# main.net
KiCad netlist of a schematic drawn in Altium Designer
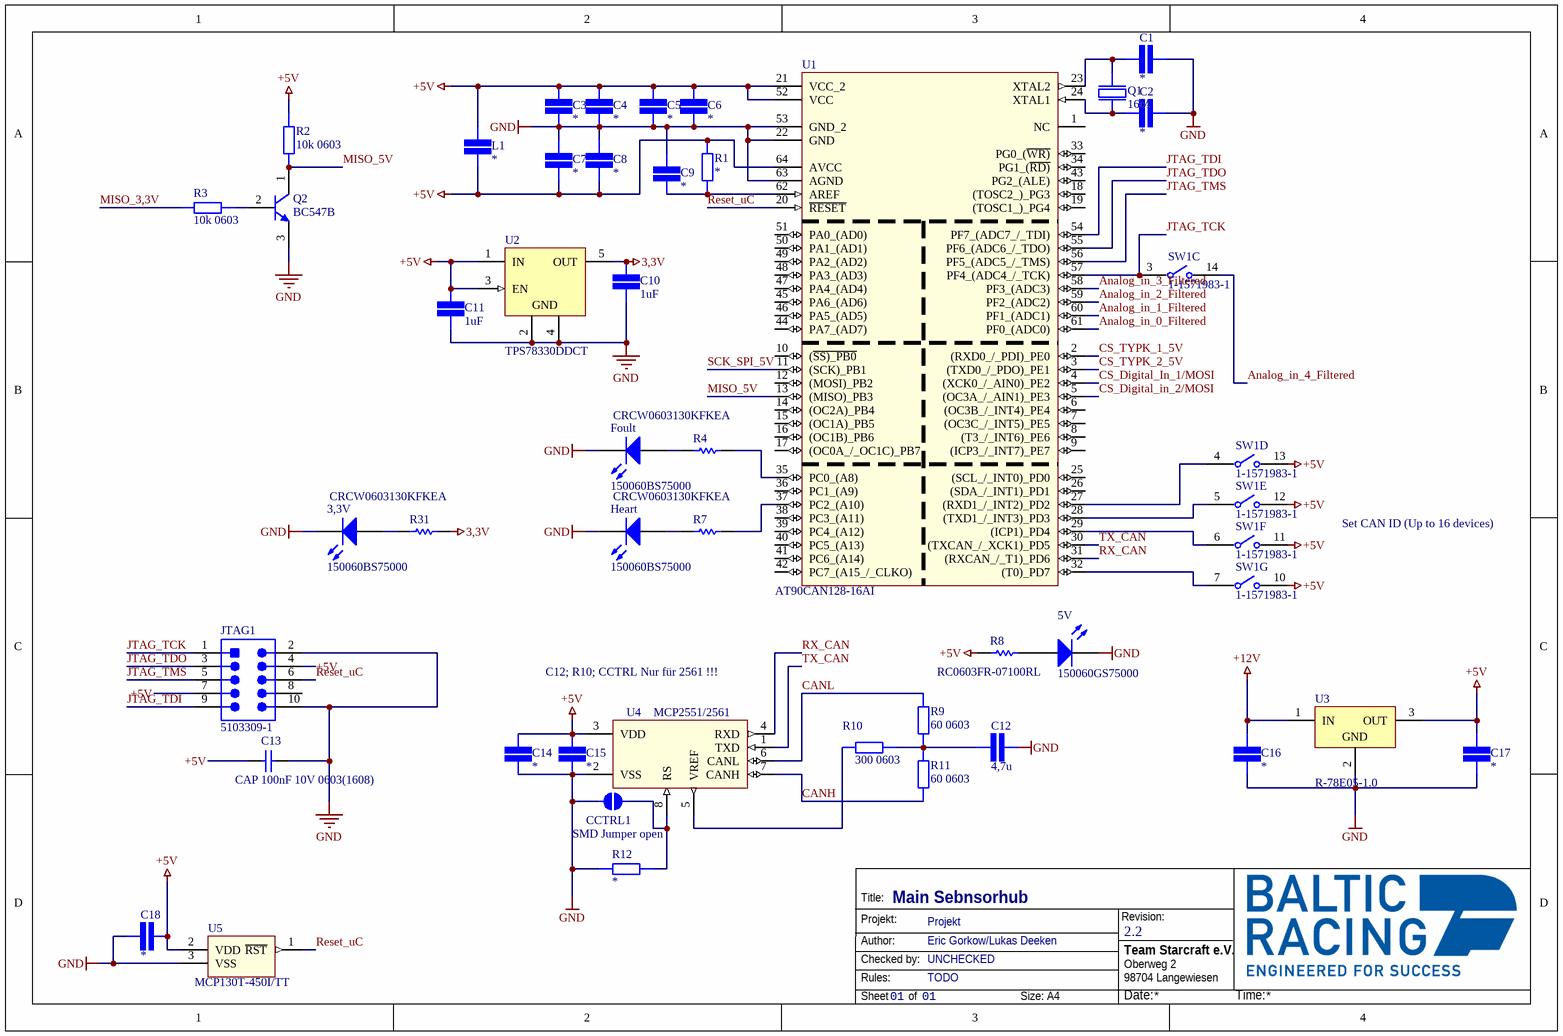
[diagram p0: main.SchDoc]

(export (version "E")
  (design (tool "Eeschema 10.0.6"))
  (components
    (comp (ref "3,3V")
      (value "150060BS75000")
      (footprint "0603_A")
      (description "SMD mono-color Chip LED, WL-SMCW, Blue")
      (fields (field (name "MANUFACTURER") "Wuerth Elektronik"))
      (libsource (lib "Altium Content Vault") (part "WE-LED_K1A2-2"))
    )
    (comp (ref "5V")
      (value "150060GS75000")
      (footprint "0603_A")
      (description "SMD mono-color Chip LED, WL-SMCW, Green")
      (fields (field (name "MANUFACTURER") "Wuerth Elektronik"))
      (libsource (lib "Altium Content Vault") (part "WE-LED_K1A2-2"))
    )
    (comp (ref "C1")
      (value "SMD Capacitor")
      (footprint "CAP 0603/1608")
      (description "Capacitor with multiple Footprints")
      (fields (field (name "ALTIUM_VALUE") "*"))
      (libsource (lib "Standardbauteile") (part "SMD Capacitor"))
    )
    (comp (ref "C2")
      (value "SMD Capacitor")
      (footprint "CAP 0603/1608")
      (description "Capacitor with multiple Footprints")
      (fields (field (name "ALTIUM_VALUE") "*"))
      (libsource (lib "Standardbauteile") (part "SMD Capacitor"))
    )
    (comp (ref "C3")
      (value "SMD Capacitor")
      (footprint "CAP 0603/1608")
      (description "Capacitor with multiple Footprints")
      (fields (field (name "ALTIUM_VALUE") "*"))
      (libsource (lib "") (part "SMD Capacitor_1"))
    )
    (comp (ref "C4")
      (value "SMD Capacitor")
      (footprint "CAP 0603/1608")
      (description "Capacitor with multiple Footprints")
      (fields (field (name "ALTIUM_VALUE") "*"))
      (libsource (lib "") (part "SMD Capacitor_1"))
    )
    (comp (ref "C5")
      (value "SMD Capacitor")
      (footprint "CAP 0603/1608")
      (description "Capacitor with multiple Footprints")
      (fields (field (name "ALTIUM_VALUE") "*"))
      (libsource (lib "") (part "SMD Capacitor_1"))
    )
    (comp (ref "C6")
      (value "SMD Capacitor")
      (footprint "CAP 0603/1608")
      (description "Capacitor with multiple Footprints")
      (fields (field (name "ALTIUM_VALUE") "*"))
      (libsource (lib "") (part "SMD Capacitor_1"))
    )
    (comp (ref "C7")
      (value "SMD Capacitor")
      (footprint "CAP 0603/1608")
      (description "Capacitor with multiple Footprints")
      (fields (field (name "ALTIUM_VALUE") "*"))
      (libsource (lib "") (part "SMD Capacitor_1"))
    )
    (comp (ref "C8")
      (value "SMD Capacitor")
      (footprint "CAP 0603/1608")
      (description "Capacitor with multiple Footprints")
      (fields (field (name "ALTIUM_VALUE") "*"))
      (libsource (lib "") (part "SMD Capacitor_1"))
    )
    (comp (ref "C9")
      (value "SMD Capacitor")
      (footprint "CAP 0603/1608")
      (description "Capacitor with multiple Footprints")
      (fields (field (name "ALTIUM_VALUE") "*"))
      (libsource (lib "") (part "SMD Capacitor_1"))
    )
    (comp (ref "C10")
      (value "1uF")
      (footprint "CAP 0603/1608")
      (description "Capacitor with multiple Footprints")
      (fields (field (name "Comment") "SMD Capacitor 1uF"))
      (libsource (lib "") (part "SMD Capacitor_1"))
    )
    (comp (ref "C11")
      (value "1uF")
      (footprint "CAP 0603/1608")
      (description "Capacitor with multiple Footprints")
      (fields (field (name "Comment") "SMD Capacitor 1uF"))
      (libsource (lib "") (part "SMD Capacitor_1"))
    )
    (comp (ref "C12")
      (value "4,7u")
      (footprint "CAP 0603/1608")
      (description "Capacitor with multiple Footprints")
      (fields (field (name "Comment") "SMD Capacitor"))
      (libsource (lib "") (part "SMD Capacitor_2"))
    )
    (comp (ref "C13")
      (value "CAP 100nF 10V 0603(1608)")
      (footprint "CAPC0603(1608)100_L")
      (description "CAP 100nF 10V ±5% 0603 (1608 Metric) Thickness 1mm SMD")
      (fields (field (name "TOLERANCE") "Â±5%"))
      (libsource (lib "Altium Content Vault") (part "CAP"))
    )
    (comp (ref "C14")
      (value "SMD Capacitor")
      (footprint "CAP 0603/1608")
      (description "Capacitor with multiple Footprints")
      (fields (field (name "ALTIUM_VALUE") "*"))
      (libsource (lib "") (part "SMD Capacitor_1"))
    )
    (comp (ref "C15")
      (value "SMD Capacitor")
      (footprint "CAP 0603/1608")
      (description "Capacitor with multiple Footprints")
      (fields (field (name "ALTIUM_VALUE") "*"))
      (libsource (lib "") (part "SMD Capacitor_1"))
    )
    (comp (ref "C16")
      (value "SMD Capacitor")
      (footprint "CAP 0603/1608")
      (description "Capacitor with multiple Footprints")
      (fields (field (name "ALTIUM_VALUE") "*"))
      (libsource (lib "") (part "SMD Capacitor_1"))
    )
    (comp (ref "C17")
      (value "SMD Capacitor")
      (footprint "CAP 0603/1608")
      (description "Capacitor with multiple Footprints")
      (fields (field (name "ALTIUM_VALUE") "*"))
      (libsource (lib "") (part "SMD Capacitor_1"))
    )
    (comp (ref "C18")
      (value "SMD Capacitor")
      (footprint "CAP 0603/1608")
      (description "Capacitor with multiple Footprints")
      (fields (field (name "ALTIUM_VALUE") "*"))
      (libsource (lib "Standardbauteile") (part "SMD Capacitor"))
    )
    (comp (ref "CCTRL1")
      (value "SMD Jumper open")
      (footprint "SMD-JUMPER-OPEN")
      (libsource (lib "Standardbauteile") (part "SMD Jumper open"))
    )
    (comp (ref "Foult")
      (value "150060BS75000")
      (footprint "0603_A")
      (description "SMD mono-color Chip LED, WL-SMCW, Blue")
      (fields (field (name "MANUFACTURER") "Wuerth Elektronik"))
      (libsource (lib "Altium Content Vault") (part "WE-LED_K1A2-2"))
    )
    (comp (ref "Heart")
      (value "150060BS75000")
      (footprint "0603_A")
      (description "SMD mono-color Chip LED, WL-SMCW, Blue")
      (fields (field (name "MANUFACTURER") "Wuerth Elektronik"))
      (libsource (lib "Altium Content Vault") (part "WE-LED_K1A2-2"))
    )
    (comp (ref "JTAG1")
      (value "5103309-1")
      (footprint "TECO-5103309-1_V")
      (fields (field (name "MANUFACTURER") "TE Connectivity"))
      (libsource (lib "Altium Content Vault") (part "CN-2P-M-R10"))
    )
    (comp (ref "L1")
      (value "SMD Capacitor")
      (footprint "CAP 0603/1608")
      (description "Capacitor with multiple Footprints")
      (fields (field (name "ALTIUM_VALUE") "*"))
      (libsource (lib "") (part "SMD Capacitor_1"))
    )
    (comp (ref "Q1")
      (value "16M")
      (footprint "NDK NX5032GA")
      (description "16 MHz Quartz")
      (libsource (lib "Standardbauteile") (part "16 MHz Quartz"))
    )
    (comp (ref "Q2")
      (value "BC547B")
      (footprint "ONSC-TO-92-3-29-11")
      (description "Amplifier Transistor, NPN Silicon, 3-Pin TO-92, Bulk Box")
      (fields (field (name "MANUFACTURER") "On Semiconductor"))
      (libsource (lib "Altium Content Vault") (part "ONSC-NPN-C1B2E3-3"))
    )
    (comp (ref "R1")
      (value "SMD Resistor")
      (footprint "STACKPOLE CSR0603")
      (description "Resistor with multiple footprints")
      (fields (field (name "ALTIUM_VALUE") "*"))
      (libsource (lib "Standardbauteile") (part "SMD Resistor"))
    )
    (comp (ref "R2")
      (value "10k 0603")
      (footprint "STACKPOLE CSR0603")
      (description "Resistor with multiple footprints")
      (fields (field (name "Comment") "SMD Resistor"))
      (libsource (lib "Standardbauteile") (part "SMD Resistor"))
    )
    (comp (ref "R3")
      (value "10k 0603")
      (footprint "STACKPOLE CSR0603")
      (description "Resistor with multiple footprints")
      (fields (field (name "Comment") "SMD Resistor"))
      (libsource (lib "Standardbauteile") (part "SMD Resistor"))
    )
    (comp (ref "R4")
      (value "CRCW0603130KFKEA")
      (footprint "RESC1609X50X30NL10T20")
      (fields (field (name "MANUFACTURER") "Vishay Dale"))
      (libsource (lib "Altium Content Vault") (part "RES"))
    )
    (comp (ref "R7")
      (value "CRCW0603130KFKEA")
      (footprint "RESC1609X50X30NL10T20")
      (fields (field (name "MANUFACTURER") "Vishay Dale"))
      (libsource (lib "Altium Content Vault") (part "RES"))
    )
    (comp (ref "R8")
      (value "RC0603FR-07100RL")
      (footprint "RESC1608X55X25ML10T15")
      (description "Chip Resistor, 100 Ohm, +/- 1%, 0.1 W, -55 to 155 degC, 0603 (1608 Metric), RoHS, Tape and Reel")
      (fields (field (name "TOLERANCE") "1%") (field (name "MANUFACTURER") "Yageo"))
      (libsource (lib "Altium Content Vault") (part "RES-2"))
    )
    (comp (ref "R9")
      (value "60 0603")
      (footprint "STACKPOLE CSR0603")
      (description "Resistor with multiple footprints")
      (fields (field (name "Comment") "SMD Resistor"))
      (libsource (lib "Standardbauteile") (part "SMD Resistor"))
    )
    (comp (ref "R10")
      (value "300 0603")
      (footprint "STACKPOLE CSR0603")
      (description "Resistor with multiple footprints")
      (fields (field (name "Comment") "SMD Resistor"))
      (libsource (lib "Standardbauteile") (part "SMD Resistor"))
    )
    (comp (ref "R11")
      (value "60 0603")
      (footprint "STACKPOLE CSR0603")
      (description "Resistor with multiple footprints")
      (fields (field (name "Comment") "SMD Resistor"))
      (libsource (lib "Standardbauteile") (part "SMD Resistor"))
    )
    (comp (ref "R12")
      (value "SMD Resistor")
      (footprint "STACKPOLE CSR0603")
      (description "Resistor with multiple footprints")
      (fields (field (name "ALTIUM_VALUE") "*"))
      (libsource (lib "Standardbauteile") (part "SMD Resistor"))
    )
    (comp (ref "R31")
      (value "CRCW0603130KFKEA")
      (footprint "RESC1609X50X30NL10T20")
      (fields (field (name "MANUFACTURER") "Vishay Dale"))
      (libsource (lib "Altium Content Vault") (part "RES"))
    )
    (comp (ref "SW1")
      (value "1-1571983-1")
      (footprint "FP-1-1571983-1-MFG")
      (description "SWITCH SLIDE DIP SPST 25MA 24V")
      (fields
        (field (name "MANUFACTURER") "TE Connectivity")
        (field (name "OCTOPART") "https://octopart.com/1-1571983-1-te+connectivity-40115518")
      )
      (libsource (lib "Altium Content Vault") (part "970e54b12a704161c1b4a03f85903bf"))
    )
    (comp (ref "U1")
      (value "AT90CAN128-16AI")
      (footprint "*QFP80P1600X1600X120-64N")
      (description "Ic Mcu 8bit 128kb Flash 64tqfp")
      (fields (field (name "MF") "Microchip"))
      (libsource (lib "Eric") (part "AT90CAN128-16AI"))
    )
    (comp (ref "U2")
      (value "TPS78330DDCT")
      (footprint "DDC0005A_L")
      (fields (field (name "MANUFACTURER") "Texas Instruments"))
      (libsource (lib "Altium Content Vault") (part "TI-TPS78XXX-DDC5"))
    )
    (comp (ref "U3")
      (value "R-78E05-1.0")
      (footprint "SIP3_RECOM")
      (description "Nonisolated 5V Switchmode converter")
      (libsource (lib "Standardbauteile") (part "R-78E05-1.0"))
    )
    (comp (ref "U4")
      (value "MCP2551/2561")
      (footprint "*SOIC127P600X175-8N")
      (description "MCP2551 Series 5.5 V 1 Mb/s Surface Mount High-Speed CAN Transceiver - SOIC-8")
      (fields (field (name "MP") "MCP2551-I/SN") (field (name "MF") "Microchip"))
      (libsource (lib "Eric") (part "MCP2551-I/SN"))
    )
    (comp (ref "U5")
      (value "MCP130T-450I/TT")
      (footprint "*SOT95P237X112-3N")
      (description "System Supervisors - Power Supply Monitors with Reset Generators Open Drain Low")
      (fields (field (name "MF") "Microchip") (field (name "MP") "MCP120T-450I/TT"))
      (libsource (lib "Eric") (part "MCP130T-450I/TT"))
    )
  )
  (nets
    (net (code "1") (name "+5V") (class "Default")
      (node (ref "C11") (pin "2") (pinfunction "2_2") (pintype "passive"))
      (node (ref "C13") (pin "1") (pinfunction "1_1") (pintype "passive"))
      (node (ref "C14") (pin "2") (pinfunction "2_2") (pintype "passive"))
      (node (ref "C15") (pin "2") (pinfunction "2_2") (pintype "passive"))
      (node (ref "C17") (pin "2") (pinfunction "2_2") (pintype "passive"))
      (node (ref "C18") (pin "1") (pinfunction "1_1") (pintype "passive"))
      (node (ref "C3") (pin "2") (pinfunction "2_2") (pintype "passive"))
      (node (ref "C4") (pin "2") (pinfunction "2_2") (pintype "passive"))
      (node (ref "C5") (pin "2") (pinfunction "2_2") (pintype "passive"))
      (node (ref "C6") (pin "2") (pinfunction "2_2") (pintype "passive"))
      (node (ref "C7") (pin "1") (pinfunction "1_1") (pintype "passive"))
      (node (ref "C8") (pin "1") (pinfunction "1_1") (pintype "passive"))
      (node (ref "JTAG1") (pin "4") (pinfunction "4_4") (pintype "passive"))
      (node (ref "JTAG1") (pin "7") (pinfunction "7_7") (pintype "passive"))
      (node (ref "L1") (pin "1") (pinfunction "1_1") (pintype "passive"))
      (node (ref "L1") (pin "2") (pinfunction "2_2") (pintype "passive"))
      (node (ref "R1") (pin "2") (pinfunction "2_2") (pintype "passive"))
      (node (ref "R2") (pin "1") (pinfunction "1_1") (pintype "passive"))
      (node (ref "R8") (pin "1") (pinfunction "1_1") (pintype "passive"))
      (node (ref "SW1") (pin "10") (pinfunction "10_10") (pintype "passive"))
      (node (ref "SW1") (pin "11") (pinfunction "11_11") (pintype "passive"))
      (node (ref "SW1") (pin "12") (pinfunction "12_12") (pintype "passive"))
      (node (ref "SW1") (pin "13") (pinfunction "13_13") (pintype "passive"))
      (node (ref "U1") (pin "21") (pinfunction "VCC_2_21") (pintype "power_in"))
      (node (ref "U1") (pin "52") (pinfunction "VCC_52") (pintype "power_in"))
      (node (ref "U1") (pin "64") (pinfunction "AVCC_64") (pintype "power_in"))
      (node (ref "U2") (pin "1") (pinfunction "IN_1") (pintype "power_in"))
      (node (ref "U2") (pin "3") (pinfunction "EN_3") (pintype "input"))
      (node (ref "U3") (pin "3") (pinfunction "OUT_3") (pintype "power_in"))
      (node (ref "U4") (pin "3") (pinfunction "VDD_3") (pintype "power_in"))
      (node (ref "U5") (pin "2") (pinfunction "VDD_2") (pintype "power_in"))
    )
    (net (code "2") (name "+12V") (class "Default")
      (node (ref "C16") (pin "2") (pinfunction "2_2") (pintype "passive"))
      (node (ref "U3") (pin "1") (pinfunction "IN_1") (pintype "power_in"))
    )
    (net (code "3") (name "/Analog_in_0_Filtered") (class "Default")
      (node (ref "U1") (pin "61") (pinfunction "PF0_(ADC0)_61") (pintype "bidirectional"))
    )
    (net (code "4") (name "/Analog_in_1_Filtered") (class "Default")
      (node (ref "U1") (pin "60") (pinfunction "PF1_(ADC1)_60") (pintype "bidirectional"))
    )
    (net (code "5") (name "/Analog_in_2_Filtered") (class "Default")
      (node (ref "U1") (pin "59") (pinfunction "PF2_(ADC2)_59") (pintype "bidirectional"))
    )
    (net (code "6") (name "/Analog_in_3_Filtered") (class "Default")
      (node (ref "U1") (pin "58") (pinfunction "PF3_(ADC3)_58") (pintype "bidirectional"))
    )
    (net (code "7") (name "/Analog_in_4_Filtered") (class "Default")
      (node (ref "SW1") (pin "14") (pinfunction "14_14") (pintype "passive"))
    )
    (net (code "8") (name "/CANH") (class "Default")
      (node (ref "R11") (pin "2") (pinfunction "2_2") (pintype "passive"))
      (node (ref "U4") (pin "7") (pinfunction "CANH_7") (pintype "bidirectional"))
    )
    (net (code "9") (name "/CANL") (class "Default")
      (node (ref "R9") (pin "1") (pinfunction "1_1") (pintype "passive"))
      (node (ref "U4") (pin "6") (pinfunction "CANL_6") (pintype "bidirectional"))
    )
    (net (code "10") (name "/CS_Digital_In_1{slash}MOSI") (class "Default")
      (node (ref "U1") (pin "4") (pinfunction "(XCK0_/_AIN0)_PE2_4") (pintype "bidirectional"))
    )
    (net (code "11") (name "/CS_Digital_in_2{slash}MOSI") (class "Default")
      (node (ref "U1") (pin "5") (pinfunction "(OC3A_/_AIN1)_PE3_5") (pintype "bidirectional"))
    )
    (net (code "12") (name "/CS_TYPK_1_5V") (class "Default")
      (node (ref "U1") (pin "2") (pinfunction "(RXD0_/_PDI)_PE0_2") (pintype "bidirectional"))
    )
    (net (code "13") (name "/CS_TYPK_2_5V") (class "Default")
      (node (ref "U1") (pin "3") (pinfunction "(TXD0_/_PDO)_PE1_3") (pintype "bidirectional"))
    )
    (net (code "14") (name "/JTAG_TCK") (class "Default")
      (node (ref "JTAG1") (pin "1") (pinfunction "1_1") (pintype "passive"))
      (node (ref "SW1") (pin "3") (pinfunction "3_3") (pintype "passive"))
      (node (ref "U1") (pin "57") (pinfunction "PF4_(ADC4_/_TCK)_57") (pintype "bidirectional"))
    )
    (net (code "15") (name "/JTAG_TDI") (class "Default")
      (node (ref "JTAG1") (pin "9") (pinfunction "9_9") (pintype "passive"))
      (node (ref "U1") (pin "54") (pinfunction "PF7_(ADC7_/_TDI)_54") (pintype "bidirectional"))
    )
    (net (code "16") (name "/JTAG_TDO") (class "Default")
      (node (ref "JTAG1") (pin "3") (pinfunction "3_3") (pintype "passive"))
      (node (ref "U1") (pin "55") (pinfunction "PF6_(ADC6_/_TDO)_55") (pintype "bidirectional"))
    )
    (net (code "17") (name "/JTAG_TMS") (class "Default")
      (node (ref "JTAG1") (pin "5") (pinfunction "5_5") (pintype "passive"))
      (node (ref "U1") (pin "56") (pinfunction "PF5_(ADC5_/_TMS)_56") (pintype "bidirectional"))
    )
    (net (code "18") (name "/MISO_3,3V") (class "Default")
      (node (ref "R3") (pin "1") (pinfunction "1_1") (pintype "passive"))
    )
    (net (code "19") (name "/MISO_5V") (class "Default")
      (node (ref "Q2") (pin "1") (pinfunction "C_1") (pintype "passive"))
      (node (ref "R2") (pin "2") (pinfunction "2_2") (pintype "passive"))
      (node (ref "U1") (pin "13") (pinfunction "(MISO)_PB3_13") (pintype "bidirectional"))
    )
    (net (code "20") (name "/RX_CAN") (class "Default")
      (node (ref "U1") (pin "31") (pinfunction "(RXCAN_/_T1)_PD6_31") (pintype "bidirectional"))
      (node (ref "U4") (pin "4") (pinfunction "RXD_4") (pintype "output"))
    )
    (net (code "21") (name "/Reset_uC") (class "Default")
      (node (ref "JTAG1") (pin "6") (pinfunction "6_6") (pintype "passive"))
      (node (ref "U1") (pin "20") (pinfunction "~{RESET}_20") (pintype "input"))
      (node (ref "U5") (pin "1") (pinfunction "~{RST}_1") (pintype "output"))
    )
    (net (code "22") (name "/SCK_SPI_5V") (class "Default")
      (node (ref "U1") (pin "11") (pinfunction "(SCK)_PB1_11") (pintype "bidirectional"))
    )
    (net (code "23") (name "/TX_CAN") (class "Default")
      (node (ref "U1") (pin "30") (pinfunction "(TXCAN_/_XCK1)_PD5_30") (pintype "bidirectional"))
      (node (ref "U4") (pin "1") (pinfunction "TXD_1") (pintype "input"))
    )
    (net (code "24") (name "3,3V") (class "Default")
      (node (ref "C10") (pin "2") (pinfunction "2_2") (pintype "passive"))
      (node (ref "R31") (pin "1") (pinfunction "1_1") (pintype "passive"))
      (node (ref "U2") (pin "5") (pinfunction "OUT_5") (pintype "power_in"))
    )
    (net (code "25") (name "GND") (class "Default")
      (node (ref "3,3V") (pin "1") (pinfunction "K_1") (pintype "passive"))
      (node (ref "5V") (pin "1") (pinfunction "K_1") (pintype "passive"))
      (node (ref "C1") (pin "1") (pinfunction "1_1") (pintype "passive"))
      (node (ref "C10") (pin "1") (pinfunction "1_1") (pintype "passive"))
      (node (ref "C11") (pin "1") (pinfunction "1_1") (pintype "passive"))
      (node (ref "C12") (pin "2") (pinfunction "2_2") (pintype "passive"))
      (node (ref "C13") (pin "2") (pinfunction "2_2") (pintype "passive"))
      (node (ref "C14") (pin "1") (pinfunction "1_1") (pintype "passive"))
      (node (ref "C15") (pin "1") (pinfunction "1_1") (pintype "passive"))
      (node (ref "C16") (pin "1") (pinfunction "1_1") (pintype "passive"))
      (node (ref "C17") (pin "1") (pinfunction "1_1") (pintype "passive"))
      (node (ref "C18") (pin "2") (pinfunction "2_2") (pintype "passive"))
      (node (ref "C2") (pin "1") (pinfunction "1_1") (pintype "passive"))
      (node (ref "C3") (pin "1") (pinfunction "1_1") (pintype "passive"))
      (node (ref "C4") (pin "1") (pinfunction "1_1") (pintype "passive"))
      (node (ref "C5") (pin "1") (pinfunction "1_1") (pintype "passive"))
      (node (ref "C6") (pin "1") (pinfunction "1_1") (pintype "passive"))
      (node (ref "C7") (pin "2") (pinfunction "2_2") (pintype "passive"))
      (node (ref "C8") (pin "2") (pinfunction "2_2") (pintype "passive"))
      (node (ref "C9") (pin "2") (pinfunction "2_2") (pintype "passive"))
      (node (ref "CCTRL1") (pin "1") (pinfunction "1_1") (pintype "passive"))
      (node (ref "Foult") (pin "1") (pinfunction "K_1") (pintype "passive"))
      (node (ref "Heart") (pin "1") (pinfunction "K_1") (pintype "passive"))
      (node (ref "JTAG1") (pin "10") (pinfunction "10_10") (pintype "passive"))
      (node (ref "JTAG1") (pin "2") (pinfunction "2_2") (pintype "passive"))
      (node (ref "Q2") (pin "3") (pinfunction "E_3") (pintype "passive"))
      (node (ref "R12") (pin "1") (pinfunction "1_1") (pintype "passive"))
      (node (ref "U1") (pin "22") (pinfunction "GND_22") (pintype "passive"))
      (node (ref "U1") (pin "53") (pinfunction "GND_2_53") (pintype "passive"))
      (node (ref "U1") (pin "63") (pinfunction "AGND_63") (pintype "passive"))
      (node (ref "U2") (pin "2") (pinfunction "GND_2") (pintype "power_in"))
      (node (ref "U2") (pin "4") (pinfunction "GND_4") (pintype "power_in"))
      (node (ref "U3") (pin "2") (pinfunction "GND_2") (pintype "power_in"))
      (node (ref "U4") (pin "2") (pinfunction "VSS_2") (pintype "passive"))
      (node (ref "U5") (pin "3") (pinfunction "VSS_3") (pintype "power_in"))
    )
    (net (code "26") (name "Net-(3,3V-A)") (class "Default")
      (node (ref "3,3V") (pin "2") (pinfunction "A_2") (pintype "passive"))
      (node (ref "R31") (pin "2") (pinfunction "2_2") (pintype "passive"))
    )
    (net (code "27") (name "Net-(5V-A)") (class "Default")
      (node (ref "5V") (pin "2") (pinfunction "A_2") (pintype "passive"))
      (node (ref "R8") (pin "2") (pinfunction "2_2") (pintype "passive"))
    )
    (net (code "28") (name "Net-(C12-Pad1)") (class "Default")
      (node (ref "C12") (pin "1") (pinfunction "1_1") (pintype "passive"))
      (node (ref "R10") (pin "2") (pinfunction "2_2") (pintype "passive"))
      (node (ref "R11") (pin "1") (pinfunction "1_1") (pintype "passive"))
      (node (ref "R9") (pin "2") (pinfunction "2_2") (pintype "passive"))
    )
    (net (code "29") (name "Net-(Foult-A)") (class "Default")
      (node (ref "Foult") (pin "2") (pinfunction "A_2") (pintype "passive"))
      (node (ref "R4") (pin "2") (pinfunction "2_2") (pintype "passive"))
    )
    (net (code "30") (name "Net-(Heart-A)") (class "Default")
      (node (ref "Heart") (pin "2") (pinfunction "A_2") (pintype "passive"))
      (node (ref "R7") (pin "2") (pinfunction "2_2") (pintype "passive"))
    )
    (net (code "31") (name "Net-(Q2-B)") (class "Default")
      (node (ref "Q2") (pin "2") (pinfunction "B_2") (pintype "passive"))
      (node (ref "R3") (pin "2") (pinfunction "2_2") (pintype "passive"))
    )
    (net (code "32") (name "Net-(U1-(ICP1)_PD4)") (class "Default")
      (node (ref "SW1") (pin "6") (pinfunction "6_6") (pintype "passive"))
      (node (ref "U1") (pin "29") (pinfunction "(ICP1)_PD4_29") (pintype "bidirectional"))
    )
    (net (code "33") (name "Net-(U1-(RXD1_{slash}_INT2)_PD2)") (class "Default")
      (node (ref "SW1") (pin "4") (pinfunction "4_4") (pintype "passive"))
      (node (ref "U1") (pin "27") (pinfunction "(RXD1_/_INT2)_PD2_27") (pintype "bidirectional"))
    )
    (net (code "34") (name "Net-(U1-(T0)_PD7)") (class "Default")
      (node (ref "SW1") (pin "7") (pinfunction "7_7") (pintype "passive"))
      (node (ref "U1") (pin "32") (pinfunction "(T0)_PD7_32") (pintype "bidirectional"))
    )
    (net (code "35") (name "Net-(U1-(TXD1_{slash}_INT3)_PD3)") (class "Default")
      (node (ref "SW1") (pin "5") (pinfunction "5_5") (pintype "passive"))
      (node (ref "U1") (pin "28") (pinfunction "(TXD1_/_INT3)_PD3_28") (pintype "bidirectional"))
    )
    (net (code "36") (name "Net-(U1-AREF)") (class "Default")
      (node (ref "C9") (pin "1") (pinfunction "1_1") (pintype "passive"))
      (node (ref "R1") (pin "1") (pinfunction "1_1") (pintype "passive"))
      (node (ref "U1") (pin "62") (pinfunction "AREF_62") (pintype "input"))
    )
    (net (code "37") (name "Net-(U1-PC0_(A8))") (class "Default")
      (node (ref "R4") (pin "1") (pinfunction "1_1") (pintype "passive"))
      (node (ref "U1") (pin "35") (pinfunction "PC0_(A8)_35") (pintype "bidirectional"))
    )
    (net (code "38") (name "Net-(U1-PC2_(A10))") (class "Default")
      (node (ref "R7") (pin "1") (pinfunction "1_1") (pintype "passive"))
      (node (ref "U1") (pin "37") (pinfunction "PC2_(A10)_37") (pintype "bidirectional"))
    )
    (net (code "39") (name "Net-(U1-XTAL1)") (class "Default")
      (node (ref "C2") (pin "2") (pinfunction "2_2") (pintype "passive"))
      (node (ref "Q1") (pin "1") (pinfunction "1_1") (pintype "passive"))
      (node (ref "U1") (pin "24") (pinfunction "XTAL1_24") (pintype "input"))
    )
    (net (code "40") (name "Net-(U1-XTAL2)") (class "Default")
      (node (ref "C1") (pin "2") (pinfunction "2_2") (pintype "passive"))
      (node (ref "Q1") (pin "2") (pinfunction "2_2") (pintype "passive"))
      (node (ref "U1") (pin "23") (pinfunction "XTAL2_23") (pintype "output"))
    )
    (net (code "41") (name "Net-(U4-RS)") (class "Default")
      (node (ref "CCTRL1") (pin "2") (pinfunction "2_2") (pintype "passive"))
      (node (ref "R12") (pin "2") (pinfunction "2_2") (pintype "passive"))
      (node (ref "U4") (pin "8") (pinfunction "RS_8") (pintype "input"))
    )
    (net (code "42") (name "Net-(U4-VREF)") (class "Default")
      (node (ref "R10") (pin "1") (pinfunction "1_1") (pintype "passive"))
      (node (ref "U4") (pin "5") (pinfunction "VREF_5") (pintype "output"))
    )
    (net (code "43") (name "unconnected-(JTAG1-Pad8)") (class "Default")
      (node (ref "JTAG1") (pin "8") (pinfunction "8_8") (pintype "passive"))
    )
    (net (code "44") (name "unconnected-(U1-(ICP3_{slash}_INT7)_PE7-Pad9)") (class "Default")
      (node (ref "U1") (pin "9") (pinfunction "(ICP3_/_INT7)_PE7_9") (pintype "bidirectional"))
    )
    (net (code "45") (name "unconnected-(U1-(MOSI)_PB2-Pad12)") (class "Default")
      (node (ref "U1") (pin "12") (pinfunction "(MOSI)_PB2_12") (pintype "bidirectional"))
    )
    (net (code "46") (name "unconnected-(U1-(OC0A_{slash}_OC1C)_PB7-Pad17)") (class "Default")
      (node (ref "U1") (pin "17") (pinfunction "(OC0A_/_OC1C)_PB7_17") (pintype "bidirectional"))
    )
    (net (code "47") (name "unconnected-(U1-(OC1A)_PB5-Pad15)") (class "Default")
      (node (ref "U1") (pin "15") (pinfunction "(OC1A)_PB5_15") (pintype "bidirectional"))
    )
    (net (code "48") (name "unconnected-(U1-(OC1B)_PB6-Pad16)") (class "Default")
      (node (ref "U1") (pin "16") (pinfunction "(OC1B)_PB6_16") (pintype "bidirectional"))
    )
    (net (code "49") (name "unconnected-(U1-(OC2A)_PB4-Pad14)") (class "Default")
      (node (ref "U1") (pin "14") (pinfunction "(OC2A)_PB4_14") (pintype "bidirectional"))
    )
    (net (code "50") (name "unconnected-(U1-(OC3B_{slash}_INT4)_PE4-Pad6)") (class "Default")
      (node (ref "U1") (pin "6") (pinfunction "(OC3B_/_INT4)_PE4_6") (pintype "bidirectional"))
    )
    (net (code "51") (name "unconnected-(U1-(OC3C_{slash}_INT5)_PE5-Pad7)") (class "Default")
      (node (ref "U1") (pin "7") (pinfunction "(OC3C_/_INT5)_PE5_7") (pintype "bidirectional"))
    )
    (net (code "52") (name "unconnected-(U1-(SCL_{slash}_INT0)_PD0-Pad25)") (class "Default")
      (node (ref "U1") (pin "25") (pinfunction "(SCL_/_INT0)_PD0_25") (pintype "bidirectional"))
    )
    (net (code "53") (name "unconnected-(U1-(SDA_{slash}_INT1)_PD1-Pad26)") (class "Default")
      (node (ref "U1") (pin "26") (pinfunction "(SDA_/_INT1)_PD1_26") (pintype "bidirectional"))
    )
    (net (code "54") (name "unconnected-(U1-(T3_{slash}_INT6)_PE6-Pad8)") (class "Default")
      (node (ref "U1") (pin "8") (pinfunction "(T3_/_INT6)_PE6_8") (pintype "bidirectional"))
    )
    (net (code "55") (name "unconnected-(U1-(TOSC1_)_PG4-Pad19)") (class "Default")
      (node (ref "U1") (pin "19") (pinfunction "(TOSC1_)_PG4_19") (pintype "bidirectional"))
    )
    (net (code "56") (name "unconnected-(U1-(TOSC2_)_PG3-Pad18)") (class "Default")
      (node (ref "U1") (pin "18") (pinfunction "(TOSC2_)_PG3_18") (pintype "bidirectional"))
    )
    (net (code "57") (name "unconnected-(U1-(~{SS)_PB0}-Pad10)") (class "Default")
      (node (ref "U1") (pin "10") (pinfunction "(~{SS)_PB0}_10") (pintype "bidirectional"))
    )
    (net (code "58") (name "unconnected-(U1-NC-Pad1)") (class "Default")
      (node (ref "U1") (pin "1") (pinfunction "NC_1") (pintype "passive"))
    )
    (net (code "59") (name "unconnected-(U1-PA0_(AD0)-Pad51)") (class "Default")
      (node (ref "U1") (pin "51") (pinfunction "PA0_(AD0)_51") (pintype "bidirectional"))
    )
    (net (code "60") (name "unconnected-(U1-PA1_(AD1)-Pad50)") (class "Default")
      (node (ref "U1") (pin "50") (pinfunction "PA1_(AD1)_50") (pintype "bidirectional"))
    )
    (net (code "61") (name "unconnected-(U1-PA2_(AD2)-Pad49)") (class "Default")
      (node (ref "U1") (pin "49") (pinfunction "PA2_(AD2)_49") (pintype "bidirectional"))
    )
    (net (code "62") (name "unconnected-(U1-PA3_(AD3)-Pad48)") (class "Default")
      (node (ref "U1") (pin "48") (pinfunction "PA3_(AD3)_48") (pintype "bidirectional"))
    )
    (net (code "63") (name "unconnected-(U1-PA4_(AD4)-Pad47)") (class "Default")
      (node (ref "U1") (pin "47") (pinfunction "PA4_(AD4)_47") (pintype "bidirectional"))
    )
    (net (code "64") (name "unconnected-(U1-PA5_(AD5)-Pad46)") (class "Default")
      (node (ref "U1") (pin "46") (pinfunction "PA5_(AD5)_46") (pintype "bidirectional"))
    )
    (net (code "65") (name "unconnected-(U1-PA6_(AD6)-Pad45)") (class "Default")
      (node (ref "U1") (pin "45") (pinfunction "PA6_(AD6)_45") (pintype "bidirectional"))
    )
    (net (code "66") (name "unconnected-(U1-PA7_(AD7)-Pad44)") (class "Default")
      (node (ref "U1") (pin "44") (pinfunction "PA7_(AD7)_44") (pintype "bidirectional"))
    )
    (net (code "67") (name "unconnected-(U1-PC1_(A9)-Pad36)") (class "Default")
      (node (ref "U1") (pin "36") (pinfunction "PC1_(A9)_36") (pintype "bidirectional"))
    )
    (net (code "68") (name "unconnected-(U1-PC3_(A11)-Pad38)") (class "Default")
      (node (ref "U1") (pin "38") (pinfunction "PC3_(A11)_38") (pintype "bidirectional"))
    )
    (net (code "69") (name "unconnected-(U1-PC4_(A12)-Pad39)") (class "Default")
      (node (ref "U1") (pin "39") (pinfunction "PC4_(A12)_39") (pintype "bidirectional"))
    )
    (net (code "70") (name "unconnected-(U1-PC5_(A13)-Pad40)") (class "Default")
      (node (ref "U1") (pin "40") (pinfunction "PC5_(A13)_40") (pintype "bidirectional"))
    )
    (net (code "71") (name "unconnected-(U1-PC6_(A14)-Pad41)") (class "Default")
      (node (ref "U1") (pin "41") (pinfunction "PC6_(A14)_41") (pintype "bidirectional"))
    )
    (net (code "72") (name "unconnected-(U1-PC7_(A15_{slash}_CLKO)-Pad42)") (class "Default")
      (node (ref "U1") (pin "42") (pinfunction "PC7_(A15_/_CLKO)_42") (pintype "bidirectional"))
    )
    (net (code "73") (name "unconnected-(U1-PG0_(~{WR)}-Pad33)") (class "Default")
      (node (ref "U1") (pin "33") (pinfunction "PG0_(~{WR)}_33") (pintype "bidirectional"))
    )
    (net (code "74") (name "unconnected-(U1-PG1_(~{RD)}-Pad34)") (class "Default")
      (node (ref "U1") (pin "34") (pinfunction "PG1_(~{RD)}_34") (pintype "bidirectional"))
    )
    (net (code "75") (name "unconnected-(U1-PG2_(ALE)-Pad43)") (class "Default")
      (node (ref "U1") (pin "43") (pinfunction "PG2_(ALE)_43") (pintype "bidirectional"))
    )
  )
)
